# 04_Z-WAVE.net
KiCad netlist of a schematic drawn in Altium Designer
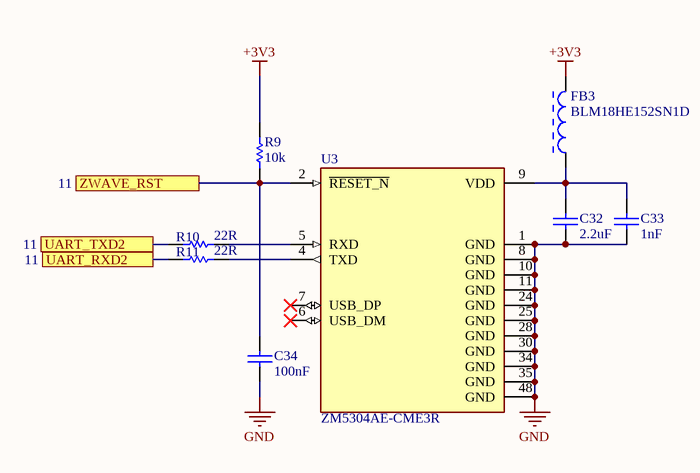
[diagram p0: 04. Z-WAVE.SchDoc]

(export (version "E")
  (design (tool "Eeschema 10.0.6"))
  (components
    (comp (ref "C32")
      (value "2.2uF")
      (footprint "CAPC1608X90X35NL10T15")
      (fields (field (name "MANUFACTURER") "Murata") (field (name "PART NUMBER") "GCM188R70J225KE22D"))
      (libsource (lib "Altium Content Vault") (part "CAP"))
    )
    (comp (ref "C33")
      (value "1nF")
      (footprint "CAPC1005X55X25NL05T10")
      (fields (field (name "PART NUMBER") "GRM1555C1H102JA01D") (field (name "MANUFACTURER") "Murata"))
      (libsource (lib "Altium Content Vault") (part "CAP"))
    )
    (comp (ref "C34")
      (value "100nF")
      (footprint "CAPC1005X56X25NL10T15")
      (fields
        (field (name "MANUFACTURER") "AVX Interconnect / Elco")
        (field (name "PART NUMBER") "04026D104KAT2A")
      )
      (libsource (lib "Altium Content Vault") (part "CAP"))
    )
    (comp (ref "FB3")
      (value "BLM18HE152SN1D")
      (footprint "MURA-BLM18-RF-H4-CHIP-2_V")
      (fields (field (name "MANUFACTURER") "Murata"))
      (libsource (lib "Altium Content Vault") (part "MURA-FB-2"))
    )
    (comp (ref "R9")
      (value "10k")
      (footprint "RESC1005X40X25NL05T05")
      (fields (field (name "MANUFACTURER") "Vishay Dale") (field (name "PART NUMBER") "CRCW040210K0FKED"))
      (libsource (lib "Altium Content Vault") (part "RES"))
    )
    (comp (ref "R10")
      (value "22R")
      (footprint "RESC1005X40X25NL05T05")
      (fields (field (name "MANUFACTURER") "Vishay Dale") (field (name "PART NUMBER") "CRCW040210K0FKED"))
      (libsource (lib "Altium Content Vault") (part "RES"))
    )
    (comp (ref "R11")
      (value "22R")
      (footprint "RESC1005X40X25NL05T05")
      (fields (field (name "MANUFACTURER") "Vishay Dale") (field (name "PART NUMBER") "CRCW040210K0FKED"))
      (libsource (lib "Altium Content Vault") (part "RES"))
    )
    (comp (ref "U3")
      (value "ZM5304AE-CME3R")
      (footprint "ZM5304AE-CME3")
      (description "General ISM < 1GHz Z-WaveÂ® Transceiver Module 868MHz Surface Mount")
      (fields (field (name "MF") "Silicon Labs") (field (name "DIGI-KEY_PART_NUMBER") "703-1074-1-ND"))
      (libsource (lib "SyTungNguyen") (part "ZM5304AE-CME3R"))
    )
  )
  (nets
    (net (code "1") (name "+3V3") (class "Default")
      (node (ref "FB3") (pin "2") (pinfunction "2_2") (pintype "passive"))
      (node (ref "R9") (pin "2") (pinfunction "2_2") (pintype "passive"))
    )
    (net (code "2") (name "/UART_RXD2") (class "Default")
      (node (ref "R11") (pin "2") (pinfunction "2_2") (pintype "passive"))
    )
    (net (code "3") (name "/UART_TXD2") (class "Default")
      (node (ref "R10") (pin "2") (pinfunction "2_2") (pintype "passive"))
    )
    (net (code "4") (name "/ZWAVE_RST") (class "Default")
      (node (ref "C34") (pin "2") (pinfunction "2_2") (pintype "passive"))
      (node (ref "R9") (pin "1") (pinfunction "1_1") (pintype "passive"))
      (node (ref "U3") (pin "2") (pinfunction "~{RESET_N}_2") (pintype "input"))
    )
    (net (code "5") (name "GND") (class "Default")
      (node (ref "C32") (pin "1") (pinfunction "1_1") (pintype "passive"))
      (node (ref "C33") (pin "1") (pinfunction "1_1") (pintype "passive"))
      (node (ref "C34") (pin "1") (pinfunction "1_1") (pintype "passive"))
      (node (ref "U3") (pin "1") (pinfunction "GND_1") (pintype "power_in"))
      (node (ref "U3") (pin "10") (pinfunction "GND_10") (pintype "power_in"))
      (node (ref "U3") (pin "11") (pinfunction "GND_11") (pintype "power_in"))
      (node (ref "U3") (pin "24") (pinfunction "GND_24") (pintype "power_in"))
      (node (ref "U3") (pin "25") (pinfunction "GND_25") (pintype "power_in"))
      (node (ref "U3") (pin "28") (pinfunction "GND_28") (pintype "power_in"))
      (node (ref "U3") (pin "30") (pinfunction "GND_30") (pintype "power_in"))
      (node (ref "U3") (pin "34") (pinfunction "GND_34") (pintype "power_in"))
      (node (ref "U3") (pin "35") (pinfunction "GND_35") (pintype "power_in"))
      (node (ref "U3") (pin "48") (pinfunction "GND_48") (pintype "power_in"))
      (node (ref "U3") (pin "8") (pinfunction "GND_8") (pintype "power_in"))
    )
    (net (code "6") (name "Net-(U3-RXD)") (class "Default")
      (node (ref "R10") (pin "1") (pinfunction "1_1") (pintype "passive"))
      (node (ref "U3") (pin "5") (pinfunction "RXD_5") (pintype "input"))
    )
    (net (code "7") (name "Net-(U3-TXD)") (class "Default")
      (node (ref "R11") (pin "1") (pinfunction "1_1") (pintype "passive"))
      (node (ref "U3") (pin "4") (pinfunction "TXD_4") (pintype "output"))
    )
    (net (code "8") (name "Net-(U3-VDD)") (class "Default")
      (node (ref "C32") (pin "2") (pinfunction "2_2") (pintype "passive"))
      (node (ref "C33") (pin "2") (pinfunction "2_2") (pintype "passive"))
      (node (ref "FB3") (pin "1") (pinfunction "1_1") (pintype "passive"))
      (node (ref "U3") (pin "9") (pinfunction "VDD_9") (pintype "power_in"))
    )
    (net (code "9") (name "unconnected-(U3-USB_DM-Pad6)") (class "Default")
      (node (ref "U3") (pin "6") (pinfunction "USB_DM_6") (pintype "bidirectional+no_connect"))
    )
    (net (code "10") (name "unconnected-(U3-USB_DP-Pad7)") (class "Default")
      (node (ref "U3") (pin "7") (pinfunction "USB_DP_7") (pintype "bidirectional+no_connect"))
    )
  )
)
